# Infinity_Camera.net
KiCad netlist of a schematic drawn in EAGLE
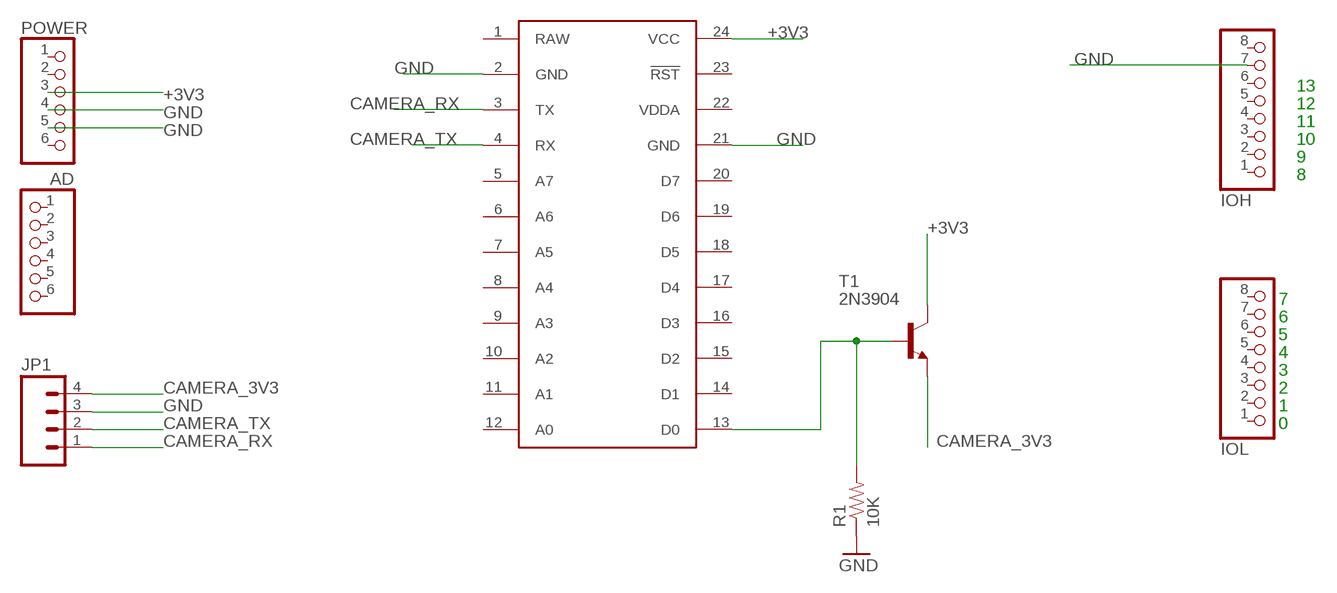
[diagram p0: schematic, sheet 1]

(export (version "E")
  (design (tool "Eeschema 10.0.6"))
  (components
    (comp (ref "AD")
      (value "PINHD-1X6")
      (footprint "eagle-import:1X06")
      (libsource (lib "eagle-import") (part "PINHD-1X6"))
    )
    (comp (ref "IOH")
      (value "PINHD-1X8")
      (footprint "eagle-import:1X08")
      (libsource (lib "eagle-import") (part "PINHD-1X8"))
    )
    (comp (ref "IOL")
      (value "PINHD-1X8")
      (footprint "eagle-import:1X08")
      (libsource (lib "eagle-import") (part "PINHD-1X8"))
    )
    (comp (ref "JP1")
      (value "M04PTH")
      (footprint "eagle-import:1X04")
      (libsource (lib "eagle-import") (part "M04PTH"))
    )
    (comp (ref "POWER")
      (value "PINHD-1X6")
      (footprint "eagle-import:1X06")
      (libsource (lib "eagle-import") (part "PINHD-1X6"))
    )
    (comp (ref "R1")
      (value "10K")
      (footprint "eagle-import:AXIAL-0.4")
      (libsource (lib "eagle-import") (part "RESISTORPTH-1/4W"))
    )
    (comp (ref "T1")
      (value "2N3904")
      (footprint "eagle-import:TO92")
      (libsource (lib "eagle-import") (part "2N3904"))
    )
    (comp (ref "U$1")
      (value "SPARK_CORECORE")
      (footprint "eagle-import:SPARK_CORE")
      (libsource (lib "eagle-import") (part "SPARK_CORECORE"))
    )
  )
  (nets
    (net (code "1") (name "/+3V3") (class "Default")
      (node (ref "POWER") (pin "3") (pinfunction "3_3") (pintype "passive"))
      (node (ref "T1") (pin "1") (pinfunction "C_1") (pintype "passive"))
      (node (ref "U$1") (pin "24") (pinfunction "VCC_24") (pintype "power_in"))
    )
    (net (code "2") (name "/CAMERA_3V3") (class "Default")
      (node (ref "JP1") (pin "4") (pinfunction "4_4") (pintype "passive"))
      (node (ref "T1") (pin "3") (pinfunction "E_3") (pintype "passive"))
    )
    (net (code "3") (name "/CAMERA_RX") (class "Default")
      (node (ref "JP1") (pin "1") (pinfunction "1_1") (pintype "passive"))
      (node (ref "U$1") (pin "3") (pinfunction "TX_3") (pintype "bidirectional"))
    )
    (net (code "4") (name "/CAMERA_TX") (class "Default")
      (node (ref "JP1") (pin "2") (pinfunction "2_2") (pintype "passive"))
      (node (ref "U$1") (pin "4") (pinfunction "RX_4") (pintype "bidirectional"))
    )
    (net (code "5") (name "/RAW") (class "Default")
      (node (ref "U$1") (pin "1") (pinfunction "RAW_1") (pintype "power_in"))
    )
    (net (code "6") (name "/VDDA") (class "Default")
      (node (ref "U$1") (pin "22") (pinfunction "VDDA_22") (pintype "power_in"))
    )
    (net (code "7") (name "GND") (class "Default")
      (node (ref "IOH") (pin "7") (pinfunction "7_7") (pintype "passive"))
      (node (ref "JP1") (pin "3") (pinfunction "3_3") (pintype "passive"))
      (node (ref "POWER") (pin "4") (pinfunction "4_4") (pintype "passive"))
      (node (ref "POWER") (pin "5") (pinfunction "5_5") (pintype "passive"))
      (node (ref "R1") (pin "P$1") (pinfunction "1_P$1") (pintype "passive"))
      (node (ref "U$1") (pin "2") (pinfunction "GND_2") (pintype "power_in"))
      (node (ref "U$1") (pin "21") (pinfunction "GND_21") (pintype "power_in"))
    )
    (net (code "8") (name "Net-(R1-2)") (class "Default")
      (node (ref "R1") (pin "P$2") (pinfunction "2_P$2") (pintype "passive"))
      (node (ref "T1") (pin "2") (pinfunction "B_2") (pintype "passive"))
      (node (ref "U$1") (pin "13") (pinfunction "D0_13") (pintype "bidirectional"))
    )
    (net (code "9") (name "unconnected-(AD-Pad1)") (class "Default")
      (node (ref "AD") (pin "1") (pinfunction "1_1") (pintype "passive"))
    )
    (net (code "10") (name "unconnected-(AD-Pad2)") (class "Default")
      (node (ref "AD") (pin "2") (pinfunction "2_2") (pintype "passive"))
    )
    (net (code "11") (name "unconnected-(AD-Pad3)") (class "Default")
      (node (ref "AD") (pin "3") (pinfunction "3_3") (pintype "passive"))
    )
    (net (code "12") (name "unconnected-(AD-Pad4)") (class "Default")
      (node (ref "AD") (pin "4") (pinfunction "4_4") (pintype "passive"))
    )
    (net (code "13") (name "unconnected-(AD-Pad5)") (class "Default")
      (node (ref "AD") (pin "5") (pinfunction "5_5") (pintype "passive"))
    )
    (net (code "14") (name "unconnected-(AD-Pad6)") (class "Default")
      (node (ref "AD") (pin "6") (pinfunction "6_6") (pintype "passive"))
    )
    (net (code "15") (name "unconnected-(IOH-Pad1)") (class "Default")
      (node (ref "IOH") (pin "1") (pinfunction "1_1") (pintype "passive"))
    )
    (net (code "16") (name "unconnected-(IOH-Pad2)") (class "Default")
      (node (ref "IOH") (pin "2") (pinfunction "2_2") (pintype "passive"))
    )
    (net (code "17") (name "unconnected-(IOH-Pad3)") (class "Default")
      (node (ref "IOH") (pin "3") (pinfunction "3_3") (pintype "passive"))
    )
    (net (code "18") (name "unconnected-(IOH-Pad4)") (class "Default")
      (node (ref "IOH") (pin "4") (pinfunction "4_4") (pintype "passive"))
    )
    (net (code "19") (name "unconnected-(IOH-Pad5)") (class "Default")
      (node (ref "IOH") (pin "5") (pinfunction "5_5") (pintype "passive"))
    )
    (net (code "20") (name "unconnected-(IOH-Pad6)") (class "Default")
      (node (ref "IOH") (pin "6") (pinfunction "6_6") (pintype "passive"))
    )
    (net (code "21") (name "unconnected-(IOH-Pad8)") (class "Default")
      (node (ref "IOH") (pin "8") (pinfunction "8_8") (pintype "passive"))
    )
    (net (code "22") (name "unconnected-(IOL-Pad1)") (class "Default")
      (node (ref "IOL") (pin "1") (pinfunction "1_1") (pintype "passive"))
    )
    (net (code "23") (name "unconnected-(IOL-Pad2)") (class "Default")
      (node (ref "IOL") (pin "2") (pinfunction "2_2") (pintype "passive"))
    )
    (net (code "24") (name "unconnected-(IOL-Pad3)") (class "Default")
      (node (ref "IOL") (pin "3") (pinfunction "3_3") (pintype "passive"))
    )
    (net (code "25") (name "unconnected-(IOL-Pad4)") (class "Default")
      (node (ref "IOL") (pin "4") (pinfunction "4_4") (pintype "passive"))
    )
    (net (code "26") (name "unconnected-(IOL-Pad5)") (class "Default")
      (node (ref "IOL") (pin "5") (pinfunction "5_5") (pintype "passive"))
    )
    (net (code "27") (name "unconnected-(IOL-Pad6)") (class "Default")
      (node (ref "IOL") (pin "6") (pinfunction "6_6") (pintype "passive"))
    )
    (net (code "28") (name "unconnected-(IOL-Pad7)") (class "Default")
      (node (ref "IOL") (pin "7") (pinfunction "7_7") (pintype "passive"))
    )
    (net (code "29") (name "unconnected-(IOL-Pad8)") (class "Default")
      (node (ref "IOL") (pin "8") (pinfunction "8_8") (pintype "passive"))
    )
    (net (code "30") (name "unconnected-(POWER-Pad1)") (class "Default")
      (node (ref "POWER") (pin "1") (pinfunction "1_1") (pintype "passive"))
    )
    (net (code "31") (name "unconnected-(POWER-Pad2)") (class "Default")
      (node (ref "POWER") (pin "2") (pinfunction "2_2") (pintype "passive"))
    )
    (net (code "32") (name "unconnected-(POWER-Pad6)") (class "Default")
      (node (ref "POWER") (pin "6") (pinfunction "6_6") (pintype "passive"))
    )
    (net (code "33") (name "unconnected-(U$1-A0-Pad12)") (class "Default")
      (node (ref "U$1") (pin "12") (pinfunction "A0_12") (pintype "bidirectional"))
    )
    (net (code "34") (name "unconnected-(U$1-A1-Pad11)") (class "Default")
      (node (ref "U$1") (pin "11") (pinfunction "A1_11") (pintype "bidirectional"))
    )
    (net (code "35") (name "unconnected-(U$1-A2-Pad10)") (class "Default")
      (node (ref "U$1") (pin "10") (pinfunction "A2_10") (pintype "bidirectional"))
    )
    (net (code "36") (name "unconnected-(U$1-A3-Pad9)") (class "Default")
      (node (ref "U$1") (pin "9") (pinfunction "A3_9") (pintype "bidirectional"))
    )
    (net (code "37") (name "unconnected-(U$1-A4-Pad8)") (class "Default")
      (node (ref "U$1") (pin "8") (pinfunction "A4_8") (pintype "bidirectional"))
    )
    (net (code "38") (name "unconnected-(U$1-A5-Pad7)") (class "Default")
      (node (ref "U$1") (pin "7") (pinfunction "A5_7") (pintype "bidirectional"))
    )
    (net (code "39") (name "unconnected-(U$1-A6-Pad6)") (class "Default")
      (node (ref "U$1") (pin "6") (pinfunction "A6_6") (pintype "bidirectional"))
    )
    (net (code "40") (name "unconnected-(U$1-A7-Pad5)") (class "Default")
      (node (ref "U$1") (pin "5") (pinfunction "A7_5") (pintype "bidirectional"))
    )
    (net (code "41") (name "unconnected-(U$1-D1-Pad14)") (class "Default")
      (node (ref "U$1") (pin "14") (pinfunction "D1_14") (pintype "bidirectional"))
    )
    (net (code "42") (name "unconnected-(U$1-D2-Pad15)") (class "Default")
      (node (ref "U$1") (pin "15") (pinfunction "D2_15") (pintype "bidirectional"))
    )
    (net (code "43") (name "unconnected-(U$1-D3-Pad16)") (class "Default")
      (node (ref "U$1") (pin "16") (pinfunction "D3_16") (pintype "bidirectional"))
    )
    (net (code "44") (name "unconnected-(U$1-D4-Pad17)") (class "Default")
      (node (ref "U$1") (pin "17") (pinfunction "D4_17") (pintype "bidirectional"))
    )
    (net (code "45") (name "unconnected-(U$1-D5-Pad18)") (class "Default")
      (node (ref "U$1") (pin "18") (pinfunction "D5_18") (pintype "bidirectional"))
    )
    (net (code "46") (name "unconnected-(U$1-D6-Pad19)") (class "Default")
      (node (ref "U$1") (pin "19") (pinfunction "D6_19") (pintype "bidirectional"))
    )
    (net (code "47") (name "unconnected-(U$1-D7-Pad20)") (class "Default")
      (node (ref "U$1") (pin "20") (pinfunction "D7_20") (pintype "bidirectional"))
    )
    (net (code "48") (name "unconnected-(U$1-~{RST}-Pad23)") (class "Default")
      (node (ref "U$1") (pin "23") (pinfunction "~{RST}_23") (pintype "bidirectional"))
    )
  )
)
